# OPID_351_5V_Step-down_regulator.net
KiCad netlist of a schematic drawn in Altium Designer
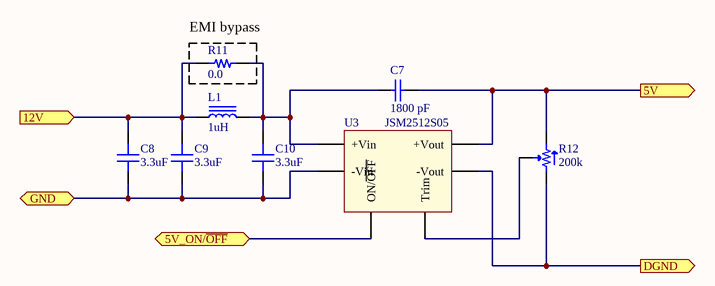
[diagram p0: OPID[351] 5V Step-down regulator.SchDoc]

(export (version "E")
  (design (tool "Eeschema 10.0.6"))
  (components
    (comp (ref "C7")
      (value "1800 pF")
      (footprint "CAP1210(3225)")
      (fields (field (name "PART NUMBER") "C1210C182JGRACTU") (field (name "TOLERANCE") "± 5%"))
      (libsource (lib "Vortex-component-database") (part "Capacitor"))
    )
    (comp (ref "C8")
      (value "3.3uF")
      (footprint "CAP 1210/3225 - 2.0MM")
      (description "CAP CER 3.3UF 25V X8L 1210")
      (fields (field (name "PART NUMBER") "C1210C335K3NACTU") (field (name "MANUFACTURER") "Kemet"))
      (libsource (lib "Celestial Library Database") (part "Capacitor"))
    )
    (comp (ref "C9")
      (value "3.3uF")
      (footprint "CAP 1210/3225 - 2.0MM")
      (description "CAP CER 3.3UF 25V X8L 1210")
      (fields (field (name "PART NUMBER") "C1210C335K3NACTU") (field (name "MANUFACTURER") "Kemet"))
      (libsource (lib "Celestial Library Database") (part "Capacitor"))
    )
    (comp (ref "C10")
      (value "3.3uF")
      (footprint "CAP 1210/3225 - 2.0MM")
      (description "CAP CER 3.3UF 25V X8L 1210")
      (fields (field (name "PART NUMBER") "C1210C335K3NACTU") (field (name "MANUFACTURER") "Kemet"))
      (libsource (lib "Celestial Library Database") (part "Capacitor"))
    )
    (comp (ref "L1")
      (value "1uH")
      (footprint "TDK VLS252012CX")
      (description "FIXED IND 1UH 2.55A 62 MOHM SMD")
      (fields (field (name "PART NUMBER") "VLS252012CX-1R0M") (field (name "MANUFACTURER") "TDK Corporation"))
      (libsource (lib "Celestial Library Database") (part "Inductor"))
    )
    (comp (ref "R11")
      (value "0.0")
      (footprint "RES 0805/2012")
      (description "RES SMD 0.0 OHM JUMPER 1/2W 0805")
      (fields (field (name "PART NUMBER") "5106") (field (name "MANUFACTURER") "Keystone Electronics"))
      (libsource (lib "Celestial Library Database") (part "Resistor"))
    )
    (comp (ref "R12")
      (value "200k")
      (footprint "POT PANASONIC EVM2W")
      (description "TRIMMER 200K OHM 0.15W SMD")
      (fields
        (field (name "PART NUMBER") "EVM-2WSX80B25")
        (field (name "MANUFACTURER") "Panasonic Electronic Components")
      )
      (libsource (lib "Celestial Library Database") (part "Potentiometer"))
    )
    (comp (ref "U3")
      (value "JSM2512S05")
      (footprint "JSM2512S05")
      (description "XP Power J Series JSM25 DC/DC Converter")
      (libsource (lib "Vortex-component-database") (part "JSM25_S"))
    )
  )
  (nets
    (net (code "1") (name "/5V") (class "Default")
      (node (ref "C7") (pin "2") (pinfunction "2_2") (pintype "passive"))
      (node (ref "R12") (pin "3") (pinfunction "3_3") (pintype "passive"))
      (node (ref "U3") (pin "3") (pinfunction "+Vout_3") (pintype "passive"))
    )
    (net (code "2") (name "/5V_ON{slash}~{OFF}") (class "Default")
      (node (ref "U3") (pin "6") (pinfunction "ON/~{OFF}_6") (pintype "passive"))
    )
    (net (code "3") (name "/12V") (class "Default")
      (node (ref "C8") (pin "2") (pinfunction "2_2") (pintype "passive"))
      (node (ref "C9") (pin "2") (pinfunction "2_2") (pintype "passive"))
      (node (ref "L1") (pin "1") (pinfunction "1_1") (pintype "passive"))
      (node (ref "R11") (pin "1") (pinfunction "1_1") (pintype "passive"))
    )
    (net (code "4") (name "/DGND") (class "Default")
      (node (ref "R12") (pin "1") (pinfunction "1_1") (pintype "passive"))
      (node (ref "U3") (pin "5") (pinfunction "-Vout_5") (pintype "passive"))
    )
    (net (code "5") (name "/GND") (class "Default")
      (node (ref "C10") (pin "1") (pinfunction "1_1") (pintype "passive"))
      (node (ref "C8") (pin "1") (pinfunction "1_1") (pintype "passive"))
      (node (ref "C9") (pin "1") (pinfunction "1_1") (pintype "passive"))
      (node (ref "U3") (pin "2") (pinfunction "-Vin_2") (pintype "passive"))
    )
    (net (code "6") (name "Net-(U3-+Vin)") (class "Default")
      (node (ref "C10") (pin "2") (pinfunction "2_2") (pintype "passive"))
      (node (ref "C7") (pin "1") (pinfunction "1_1") (pintype "passive"))
      (node (ref "L1") (pin "2") (pinfunction "2_2") (pintype "passive"))
      (node (ref "R11") (pin "2") (pinfunction "2_2") (pintype "passive"))
      (node (ref "U3") (pin "1") (pinfunction "+Vin_1") (pintype "passive"))
    )
    (net (code "7") (name "Net-(U3-Trim)") (class "Default")
      (node (ref "R12") (pin "2") (pinfunction "2_2") (pintype "passive"))
      (node (ref "U3") (pin "4") (pinfunction "Trim_4") (pintype "passive"))
    )
  )
)
